# Sheet1.net
KiCad netlist of a schematic drawn in Altium Designer
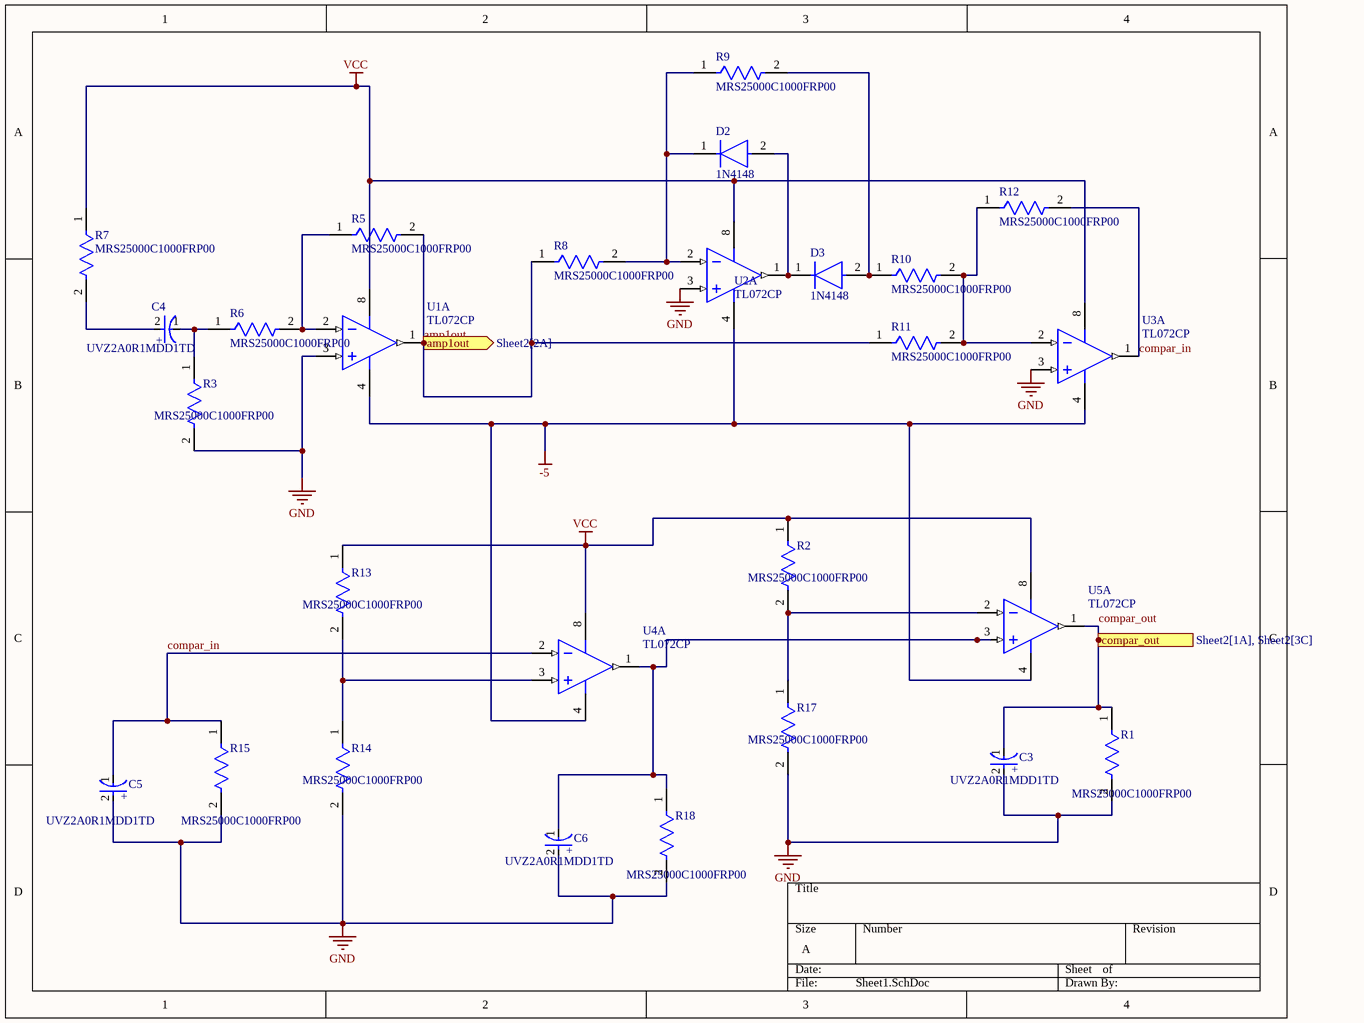
[diagram p0: Sheet1.SchDoc]

(export (version "E")
  (design (tool "Eeschema 10.0.6"))
  (components
    (comp (ref "C3")
      (value "UVZ2A0R1MDD1TD")
      (footprint "FP-UVZ2A0R1MDD1TD-MFG")
      (description "UVZ2A0R1MDD1TD Cap Alum 0.1UF 20% 100V Radial")
      (fields (field (name "TOLERANCE") "20%"))
      (libsource (lib "Altium Content Vault") (part "a00bbbee19879c290e62620ae7e47b1"))
    )
    (comp (ref "C4")
      (value "UVZ2A0R1MDD1TD")
      (footprint "FP-UVZ2A0R1MDD1TD-MFG")
      (description "UVZ2A0R1MDD1TD Cap Alum 0.1UF 20% 100V Radial")
      (fields (field (name "TOLERANCE") "20%"))
      (libsource (lib "Altium Content Vault") (part "a00bbbee19879c290e62620ae7e47b1"))
    )
    (comp (ref "C5")
      (value "UVZ2A0R1MDD1TD")
      (footprint "FP-UVZ2A0R1MDD1TD-MFG")
      (description "UVZ2A0R1MDD1TD Cap Alum 0.1UF 20% 100V Radial")
      (fields (field (name "TOLERANCE") "20%"))
      (libsource (lib "Altium Content Vault") (part "a00bbbee19879c290e62620ae7e47b1"))
    )
    (comp (ref "C6")
      (value "UVZ2A0R1MDD1TD")
      (footprint "FP-UVZ2A0R1MDD1TD-MFG")
      (description "UVZ2A0R1MDD1TD Cap Alum 0.1UF 20% 100V Radial")
      (fields (field (name "TOLERANCE") "20%"))
      (libsource (lib "Altium Content Vault") (part "a00bbbee19879c290e62620ae7e47b1"))
    )
    (comp (ref "D2")
      (value "1N4148")
      (footprint "FP-017AG-MFG")
      (description "DIODE GEN PURP 100V 200MA DO35")
      (fields (field (name "VOLTAGE") "100V"))
      (libsource (lib "Altium Content Vault") (part "d7152d700b627762746794eb795d46e"))
    )
    (comp (ref "D3")
      (value "1N4148")
      (footprint "FP-017AG-MFG")
      (description "DIODE GEN PURP 100V 200MA DO35")
      (fields (field (name "VOLTAGE") "100V"))
      (libsource (lib "Altium Content Vault") (part "d7152d700b627762746794eb795d46e"))
    )
    (comp (ref "R1")
      (value "MRS25000C1000FRP00")
      (footprint "FP-MRS25-MFG")
      (fields (field (name "TOLERANCE") "1%"))
      (libsource (lib "Altium Content Vault") (part "1029c3af85768c4190bb7ad29bc67b5"))
    )
    (comp (ref "R2")
      (value "MRS25000C1000FRP00")
      (footprint "FP-MRS25-MFG")
      (fields (field (name "TOLERANCE") "1%"))
      (libsource (lib "Altium Content Vault") (part "1029c3af85768c4190bb7ad29bc67b5"))
    )
    (comp (ref "R3")
      (value "MRS25000C1000FRP00")
      (footprint "FP-MRS25-MFG")
      (fields (field (name "TOLERANCE") "1%"))
      (libsource (lib "Altium Content Vault") (part "1029c3af85768c4190bb7ad29bc67b5"))
    )
    (comp (ref "R5")
      (value "MRS25000C1000FRP00")
      (footprint "FP-MRS25-MFG")
      (fields (field (name "TOLERANCE") "1%"))
      (libsource (lib "Altium Content Vault") (part "1029c3af85768c4190bb7ad29bc67b5"))
    )
    (comp (ref "R6")
      (value "MRS25000C1000FRP00")
      (footprint "FP-MRS25-MFG")
      (fields (field (name "TOLERANCE") "1%"))
      (libsource (lib "Altium Content Vault") (part "1029c3af85768c4190bb7ad29bc67b5"))
    )
    (comp (ref "R7")
      (value "MRS25000C1000FRP00")
      (footprint "FP-MRS25-MFG")
      (fields (field (name "TOLERANCE") "1%"))
      (libsource (lib "Altium Content Vault") (part "1029c3af85768c4190bb7ad29bc67b5"))
    )
    (comp (ref "R8")
      (value "MRS25000C1000FRP00")
      (footprint "FP-MRS25-MFG")
      (fields (field (name "TOLERANCE") "1%"))
      (libsource (lib "Altium Content Vault") (part "1029c3af85768c4190bb7ad29bc67b5"))
    )
    (comp (ref "R9")
      (value "MRS25000C1000FRP00")
      (footprint "FP-MRS25-MFG")
      (fields (field (name "TOLERANCE") "1%"))
      (libsource (lib "Altium Content Vault") (part "1029c3af85768c4190bb7ad29bc67b5"))
    )
    (comp (ref "R10")
      (value "MRS25000C1000FRP00")
      (footprint "FP-MRS25-MFG")
      (fields (field (name "TOLERANCE") "1%"))
      (libsource (lib "Altium Content Vault") (part "1029c3af85768c4190bb7ad29bc67b5"))
    )
    (comp (ref "R11")
      (value "MRS25000C1000FRP00")
      (footprint "FP-MRS25-MFG")
      (fields (field (name "TOLERANCE") "1%"))
      (libsource (lib "Altium Content Vault") (part "1029c3af85768c4190bb7ad29bc67b5"))
    )
    (comp (ref "R12")
      (value "MRS25000C1000FRP00")
      (footprint "FP-MRS25-MFG")
      (fields (field (name "TOLERANCE") "1%"))
      (libsource (lib "Altium Content Vault") (part "1029c3af85768c4190bb7ad29bc67b5"))
    )
    (comp (ref "R13")
      (value "MRS25000C1000FRP00")
      (footprint "FP-MRS25-MFG")
      (fields (field (name "TOLERANCE") "1%"))
      (libsource (lib "Altium Content Vault") (part "1029c3af85768c4190bb7ad29bc67b5"))
    )
    (comp (ref "R14")
      (value "MRS25000C1000FRP00")
      (footprint "FP-MRS25-MFG")
      (fields (field (name "TOLERANCE") "1%"))
      (libsource (lib "Altium Content Vault") (part "1029c3af85768c4190bb7ad29bc67b5"))
    )
    (comp (ref "R15")
      (value "MRS25000C1000FRP00")
      (footprint "FP-MRS25-MFG")
      (fields (field (name "TOLERANCE") "1%"))
      (libsource (lib "Altium Content Vault") (part "1029c3af85768c4190bb7ad29bc67b5"))
    )
    (comp (ref "R17")
      (value "MRS25000C1000FRP00")
      (footprint "FP-MRS25-MFG")
      (fields (field (name "TOLERANCE") "1%"))
      (libsource (lib "Altium Content Vault") (part "1029c3af85768c4190bb7ad29bc67b5"))
    )
    (comp (ref "R18")
      (value "MRS25000C1000FRP00")
      (footprint "FP-MRS25-MFG")
      (fields (field (name "TOLERANCE") "1%"))
      (libsource (lib "Altium Content Vault") (part "1029c3af85768c4190bb7ad29bc67b5"))
    )
    (comp (ref "U1")
      (value "TL072CP")
      (footprint "P0008A")
      (fields (field (name "MANUFACTURER") "Texas Instruments"))
      (libsource (lib "Altium Content Vault") (part "TI-AMP-D6-2-8_D"))
    )
    (comp (ref "U2")
      (value "TL072CP")
      (footprint "P0008A")
      (fields (field (name "MANUFACTURER") "Texas Instruments"))
      (libsource (lib "Altium Content Vault") (part "TI-AMP-D6-2-8_D"))
    )
    (comp (ref "U3")
      (value "TL072CP")
      (footprint "P0008A")
      (fields (field (name "MANUFACTURER") "Texas Instruments"))
      (libsource (lib "Altium Content Vault") (part "TI-AMP-D6-2-8_D"))
    )
    (comp (ref "U4")
      (value "TL072CP")
      (footprint "P0008A")
      (fields (field (name "MANUFACTURER") "Texas Instruments"))
      (libsource (lib "Altium Content Vault") (part "TI-AMP-D6-2-8_D"))
    )
    (comp (ref "U5")
      (value "TL072CP")
      (footprint "P0008A")
      (fields (field (name "MANUFACTURER") "Texas Instruments"))
      (libsource (lib "Altium Content Vault") (part "TI-AMP-D6-2-8_D"))
    )
  )
  (nets
    (net (code "1") (name "-5") (class "Default")
      (node (ref "U1") (pin "4") (pinfunction "VCC-_4") (pintype "power_in"))
      (node (ref "U2") (pin "4") (pinfunction "VCC-_4") (pintype "power_in"))
      (node (ref "U3") (pin "4") (pinfunction "VCC-_4") (pintype "power_in"))
      (node (ref "U4") (pin "4") (pinfunction "VCC-_4") (pintype "power_in"))
      (node (ref "U5") (pin "4") (pinfunction "VCC-_4") (pintype "power_in"))
    )
    (net (code "2") (name "/amp1out") (class "Default")
      (node (ref "R11") (pin "1") (pinfunction "1_1") (pintype "passive"))
      (node (ref "R5") (pin "2") (pinfunction "2_2") (pintype "passive"))
      (node (ref "R8") (pin "1") (pinfunction "1_1") (pintype "passive"))
      (node (ref "U1") (pin "1") (pinfunction "OUT1_1") (pintype "output"))
    )
    (net (code "3") (name "/compar_in") (class "Default")
      (node (ref "C5") (pin "1") (pinfunction "C_1") (pintype "passive"))
      (node (ref "R12") (pin "2") (pinfunction "2_2") (pintype "passive"))
      (node (ref "R15") (pin "1") (pinfunction "1_1") (pintype "passive"))
      (node (ref "U3") (pin "1") (pinfunction "OUT1_1") (pintype "output"))
      (node (ref "U4") (pin "2") (pinfunction "IN1-_2") (pintype "input"))
    )
    (net (code "4") (name "/compar_out") (class "Default")
      (node (ref "C3") (pin "1") (pinfunction "C_1") (pintype "passive"))
      (node (ref "R1") (pin "1") (pinfunction "1_1") (pintype "passive"))
      (node (ref "U5") (pin "1") (pinfunction "OUT1_1") (pintype "output"))
    )
    (net (code "5") (name "GND") (class "Default")
      (node (ref "C3") (pin "2") (pinfunction "A_2") (pintype "passive"))
      (node (ref "C5") (pin "2") (pinfunction "A_2") (pintype "passive"))
      (node (ref "C6") (pin "2") (pinfunction "A_2") (pintype "passive"))
      (node (ref "R1") (pin "2") (pinfunction "2_2") (pintype "passive"))
      (node (ref "R14") (pin "2") (pinfunction "2_2") (pintype "passive"))
      (node (ref "R15") (pin "2") (pinfunction "2_2") (pintype "passive"))
      (node (ref "R17") (pin "2") (pinfunction "2_2") (pintype "passive"))
      (node (ref "R18") (pin "2") (pinfunction "2_2") (pintype "passive"))
      (node (ref "R3") (pin "2") (pinfunction "2_2") (pintype "passive"))
      (node (ref "U1") (pin "3") (pinfunction "IN1+_3") (pintype "input"))
      (node (ref "U2") (pin "3") (pinfunction "IN1+_3") (pintype "input"))
      (node (ref "U3") (pin "3") (pinfunction "IN1+_3") (pintype "input"))
    )
    (net (code "6") (name "Net-(C4-A)") (class "Default")
      (node (ref "C4") (pin "2") (pinfunction "A_2") (pintype "passive"))
      (node (ref "R7") (pin "2") (pinfunction "2_2") (pintype "passive"))
    )
    (net (code "7") (name "Net-(C4-C)") (class "Default")
      (node (ref "C4") (pin "1") (pinfunction "C_1") (pintype "passive"))
      (node (ref "R3") (pin "1") (pinfunction "1_1") (pintype "passive"))
      (node (ref "R6") (pin "1") (pinfunction "1_1") (pintype "passive"))
    )
    (net (code "8") (name "Net-(C6-C)") (class "Default")
      (node (ref "C6") (pin "1") (pinfunction "C_1") (pintype "passive"))
      (node (ref "R18") (pin "1") (pinfunction "1_1") (pintype "passive"))
      (node (ref "U4") (pin "1") (pinfunction "OUT1_1") (pintype "output"))
      (node (ref "U5") (pin "3") (pinfunction "IN1+_3") (pintype "input"))
    )
    (net (code "9") (name "Net-(D2-A)") (class "Default")
      (node (ref "D2") (pin "2") (pinfunction "A_2") (pintype "passive"))
      (node (ref "D3") (pin "1") (pinfunction "C_1") (pintype "passive"))
      (node (ref "U2") (pin "1") (pinfunction "OUT1_1") (pintype "output"))
    )
    (net (code "10") (name "Net-(D2-C)") (class "Default")
      (node (ref "D2") (pin "1") (pinfunction "C_1") (pintype "passive"))
      (node (ref "R8") (pin "2") (pinfunction "2_2") (pintype "passive"))
      (node (ref "R9") (pin "1") (pinfunction "1_1") (pintype "passive"))
      (node (ref "U2") (pin "2") (pinfunction "IN1-_2") (pintype "input"))
    )
    (net (code "11") (name "Net-(D3-A)") (class "Default")
      (node (ref "D3") (pin "2") (pinfunction "A_2") (pintype "passive"))
      (node (ref "R10") (pin "1") (pinfunction "1_1") (pintype "passive"))
      (node (ref "R9") (pin "2") (pinfunction "2_2") (pintype "passive"))
    )
    (net (code "12") (name "Net-(U1A-IN1-)") (class "Default")
      (node (ref "R5") (pin "1") (pinfunction "1_1") (pintype "passive"))
      (node (ref "R6") (pin "2") (pinfunction "2_2") (pintype "passive"))
      (node (ref "U1") (pin "2") (pinfunction "IN1-_2") (pintype "input"))
    )
    (net (code "13") (name "Net-(U3A-IN1-)") (class "Default")
      (node (ref "R10") (pin "2") (pinfunction "2_2") (pintype "passive"))
      (node (ref "R11") (pin "2") (pinfunction "2_2") (pintype "passive"))
      (node (ref "R12") (pin "1") (pinfunction "1_1") (pintype "passive"))
      (node (ref "U3") (pin "2") (pinfunction "IN1-_2") (pintype "input"))
    )
    (net (code "14") (name "Net-(U4A-IN1+)") (class "Default")
      (node (ref "R13") (pin "2") (pinfunction "2_2") (pintype "passive"))
      (node (ref "R14") (pin "1") (pinfunction "1_1") (pintype "passive"))
      (node (ref "U4") (pin "3") (pinfunction "IN1+_3") (pintype "input"))
    )
    (net (code "15") (name "Net-(U5A-IN1-)") (class "Default")
      (node (ref "R17") (pin "1") (pinfunction "1_1") (pintype "passive"))
      (node (ref "R2") (pin "2") (pinfunction "2_2") (pintype "passive"))
      (node (ref "U5") (pin "2") (pinfunction "IN1-_2") (pintype "input"))
    )
    (net (code "16") (name "VCC") (class "Default")
      (node (ref "R13") (pin "1") (pinfunction "1_1") (pintype "passive"))
      (node (ref "R2") (pin "1") (pinfunction "1_1") (pintype "passive"))
      (node (ref "R7") (pin "1") (pinfunction "1_1") (pintype "passive"))
      (node (ref "U1") (pin "8") (pinfunction "VCC+_8") (pintype "power_in"))
      (node (ref "U2") (pin "8") (pinfunction "VCC+_8") (pintype "power_in"))
      (node (ref "U3") (pin "8") (pinfunction "VCC+_8") (pintype "power_in"))
      (node (ref "U4") (pin "8") (pinfunction "VCC+_8") (pintype "power_in"))
      (node (ref "U5") (pin "8") (pinfunction "VCC+_8") (pintype "power_in"))
    )
  )
)
